# 2_6_0.net
KiCad netlist of a schematic drawn in Altium Designer
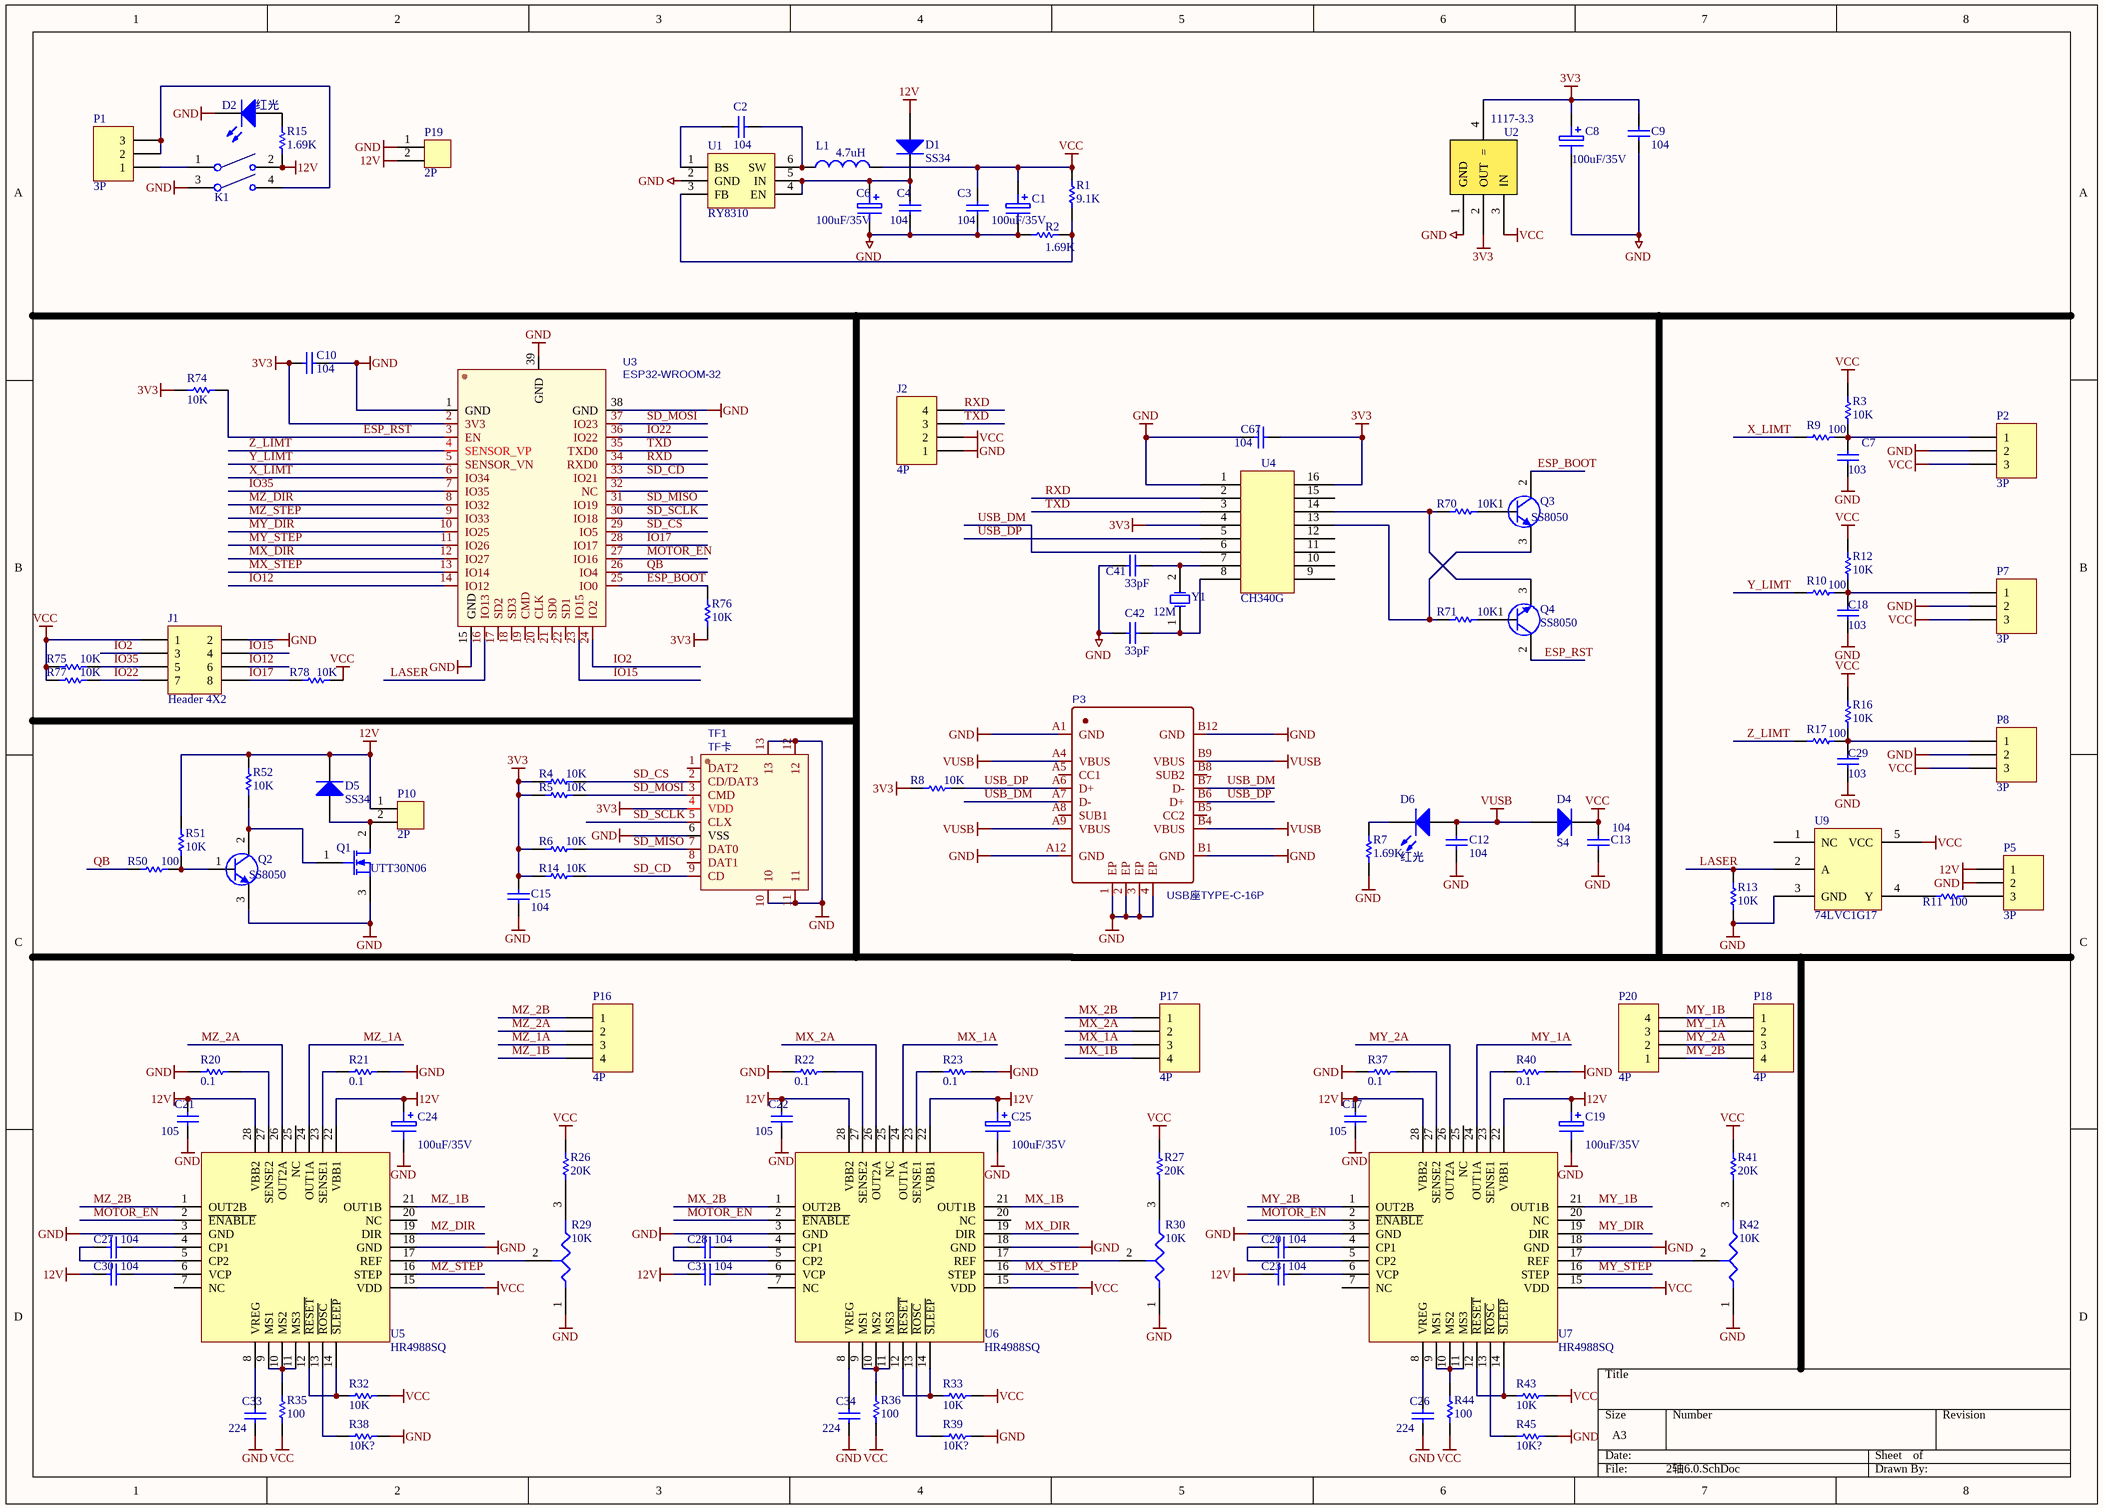
[diagram p0: 2轴6.0.SchDoc]

(export (version "E")
  (design (tool "Eeschema 10.0.6"))
  (components
    (comp (ref "C1") (value "100uF/35V") (footprint "电解电容贴片6x6") (libsource (lib "*") (part "ELECTRO1")))
    (comp (ref "C2") (value "104") (footprint "0603C") (libsource (lib "SCH封装库") (part "CAP")))
    (comp (ref "C3")
      (value "104")
      (footprint "0603C")
      (description "Capacitor (Semiconductor SIM Model)")
      (libsource (lib "Miscellaneous Devices") (part "Cap Semi"))
    )
    (comp (ref "C4") (value "104") (footprint "0603C") (libsource (lib "SCH封装库") (part "CAP")))
    (comp (ref "C6") (value "100uF/35V") (footprint "电解电容贴片6x6") (libsource (lib "*") (part "ELECTRO1")))
    (comp (ref "C7") (value "103") (footprint "0603C") (libsource (lib "SCH封装库") (part "CAP")))
    (comp (ref "C8") (value "100uF/35V") (footprint "电解电容贴片6x6") (libsource (lib "*") (part "ELECTRO1")))
    (comp (ref "C9")
      (value "104")
      (footprint "0603C")
      (description "Capacitor (Semiconductor SIM Model)")
      (libsource (lib "Miscellaneous Devices") (part "Cap Semi"))
    )
    (comp (ref "C10")
      (value "104")
      (footprint "0603C")
      (description "Capacitor (Semiconductor SIM Model)")
      (libsource (lib "Miscellaneous Devices") (part "Cap Semi"))
    )
    (comp (ref "C12")
      (value "104")
      (footprint "0603C")
      (description "Capacitor (Semiconductor SIM Model)")
      (libsource (lib "Miscellaneous Devices") (part "Cap Semi"))
    )
    (comp (ref "C13")
      (value "104")
      (footprint "0603C")
      (description "Capacitor (Semiconductor SIM Model)")
      (libsource (lib "Miscellaneous Devices") (part "Cap Semi"))
    )
    (comp (ref "C15")
      (value "104")
      (footprint "0603C")
      (description "Capacitor (Semiconductor SIM Model)")
      (libsource (lib "Miscellaneous Devices") (part "Cap Semi"))
    )
    (comp (ref "C17") (value "105") (footprint "0805C") (libsource (lib "SCH封装库") (part "CAP")))
    (comp (ref "C18") (value "103") (footprint "0603C") (libsource (lib "SCH封装库") (part "CAP")))
    (comp (ref "C19") (value "100uF/35V") (footprint "电解电容贴片6x6") (libsource (lib "*") (part "ELECTRO1")))
    (comp (ref "C20") (value "104") (footprint "0603C") (libsource (lib "SCH封装库") (part "CAP")))
    (comp (ref "C21") (value "105") (footprint "0805C") (libsource (lib "SCH封装库") (part "CAP")))
    (comp (ref "C22") (value "105") (footprint "0805C") (libsource (lib "SCH封装库") (part "CAP")))
    (comp (ref "C23") (value "104") (footprint "0603C") (libsource (lib "SCH封装库") (part "CAP")))
    (comp (ref "C24") (value "100uF/35V") (footprint "电解电容贴片6x6") (libsource (lib "*") (part "ELECTRO1")))
    (comp (ref "C25") (value "100uF/35V") (footprint "电解电容贴片6x6") (libsource (lib "*") (part "ELECTRO1")))
    (comp (ref "C26") (value "224") (footprint "0603C") (libsource (lib "SCH封装库") (part "CAP")))
    (comp (ref "C27") (value "104") (footprint "0603C") (libsource (lib "SCH封装库") (part "CAP")))
    (comp (ref "C28") (value "104") (footprint "0603C") (libsource (lib "SCH封装库") (part "CAP")))
    (comp (ref "C29") (value "103") (footprint "0603C") (libsource (lib "SCH封装库") (part "CAP")))
    (comp (ref "C30") (value "104") (footprint "0603C") (libsource (lib "SCH封装库") (part "CAP")))
    (comp (ref "C31") (value "104") (footprint "0603C") (libsource (lib "SCH封装库") (part "CAP")))
    (comp (ref "C33") (value "224") (footprint "0603C") (libsource (lib "SCH封装库") (part "CAP")))
    (comp (ref "C34") (value "224") (footprint "0603C") (libsource (lib "SCH封装库") (part "CAP")))
    (comp (ref "C41")
      (value "33pF")
      (footprint "0603C")
      (description "Capacitor (Semiconductor SIM Model)")
      (libsource (lib "Miscellaneous Devices") (part "Cap Semi"))
    )
    (comp (ref "C42")
      (value "33pF")
      (footprint "0603C")
      (description "Capacitor (Semiconductor SIM Model)")
      (libsource (lib "Miscellaneous Devices") (part "Cap Semi"))
    )
    (comp (ref "C67")
      (value "104")
      (footprint "0603C")
      (description "Capacitor (Semiconductor SIM Model)")
      (libsource (lib "Miscellaneous Devices") (part "Cap Semi"))
    )
    (comp (ref "D1") (value "SS34") (footprint "SMA") (libsource (lib "SCH封装库") (part "1N4148")))
    (comp (ref "D2") (value "红光") (footprint "0603LED") (libsource (lib "SCH封装库") (part "LED")))
    (comp (ref "D4") (value "S4") (footprint "SOD-123") (libsource (lib "SCH封装库") (part "1N4148")))
    (comp (ref "D5") (value "SS34") (footprint "SMA") (libsource (lib "SCH封装库") (part "1N4148")))
    (comp (ref "D6") (value "红光") (footprint "0603LED") (libsource (lib "SCH封装库") (part "LED")))
    (comp (ref "J1")
      (value "Header 4X2")
      (footprint "HDR2X4")
      (description "Header, 4-Pin, Dual row")
      (libsource (lib "Miscellaneous Connectors") (part "Header 4X2"))
    )
    (comp (ref "J2") (value "4P") (footprint "SIP4") (libsource (lib "") (part "4P_1")))
    (comp (ref "K1") (value "船形开关") (footprint "船形开关KCD1-104-4P") (libsource (lib "SCH封装库") (part "船形开关双刀")))
    (comp (ref "L1")
      (value "4.7uH")
      (footprint "电感贴片7x7")
      (description "Inductor")
      (libsource (lib "SCH封装库") (part "Inductor"))
    )
    (comp (ref "P1") (value "3P") (footprint "DC0044A") (libsource (lib "") (part "3P_1")))
    (comp (ref "P2") (value "3P") (footprint "HDR1X3_P") (libsource (lib "SCH封装库") (part "3P")))
    (comp (ref "P3")
      (value "USB座TYPE-C-16P")
      (footprint "USB-TYPE-C-16P")
      (fields
        (field (name "BOM_SUPPLIER PART") "C709358")
        (field (name "BOM_MANUFACTURER PART") "KH-TYPE-C-16P-T")
      )
      (libsource (lib "SCH封装库") (part "USB座TYPE-C-16P"))
    )
    (comp (ref "P5") (value "3P") (footprint "HDR1X3_P") (libsource (lib "SCH封装库") (part "3P")))
    (comp (ref "P7") (value "3P") (footprint "HDR1X3_P") (libsource (lib "SCH封装库") (part "3P")))
    (comp (ref "P8") (value "3P") (footprint "HDR1X3_P") (libsource (lib "SCH封装库") (part "3P")))
    (comp (ref "P10") (value "2P") (footprint "HDR1X2_P") (libsource (lib "SCH封装库") (part "2P")))
    (comp (ref "P16") (value "4P") (footprint "HDR1X4_P") (libsource (lib "SCH封装库") (part "4P")))
    (comp (ref "P17") (value "4P") (footprint "HDR1X4_P") (libsource (lib "SCH封装库") (part "4P")))
    (comp (ref "P18") (value "4P") (footprint "HDR1X4_P") (libsource (lib "SCH封装库") (part "4P")))
    (comp (ref "P19") (value "2P") (footprint "HDR1X2_P") (libsource (lib "SCH封装库") (part "2P")))
    (comp (ref "P20") (value "4P") (footprint "HDR1X4_P") (libsource (lib "") (part "4P_1")))
    (comp (ref "Q1")
      (value "UTT30N06")
      (footprint "TO-252")
      (description "N-Channel MOSFET")
      (libsource (lib "SCH封装库") (part "MOSFET-N"))
    )
    (comp (ref "Q2") (value "SS8050") (footprint "SOT-23") (libsource (lib "SCH封装库") (part "NPN")))
    (comp (ref "Q3") (value "SS8050") (footprint "SOT-23") (libsource (lib "SCH封装库") (part "NPN")))
    (comp (ref "Q4") (value "SS8050") (footprint "SOT-23") (libsource (lib "") (part "NPN_1")))
    (comp (ref "R1")
      (value "9.1K")
      (footprint "0603R")
      (description "Resistor")
      (libsource (lib "SCH封装库") (part "RES"))
    )
    (comp (ref "R2")
      (value "1.69K")
      (footprint "0603R")
      (description "Resistor")
      (libsource (lib "SCH封装库") (part "RES"))
    )
    (comp (ref "R3")
      (value "10K")
      (footprint "0603R")
      (description "Resistor")
      (libsource (lib "SCH封装库") (part "RES"))
    )
    (comp (ref "R4")
      (value "10K")
      (footprint "0603R")
      (description "Resistor")
      (libsource (lib "SCH封装库") (part "RES"))
    )
    (comp (ref "R5")
      (value "10K")
      (footprint "0603R")
      (description "Resistor")
      (libsource (lib "SCH封装库") (part "RES"))
    )
    (comp (ref "R6")
      (value "10K")
      (footprint "0603R")
      (description "Resistor")
      (libsource (lib "SCH封装库") (part "RES"))
    )
    (comp (ref "R7")
      (value "1.69K")
      (footprint "0603R")
      (description "Resistor")
      (libsource (lib "SCH封装库") (part "RES"))
    )
    (comp (ref "R8")
      (value "10K")
      (footprint "0603R")
      (description "Resistor")
      (libsource (lib "SCH封装库") (part "RES"))
    )
    (comp (ref "R9")
      (value "100")
      (footprint "0603R")
      (description "Resistor")
      (libsource (lib "SCH封装库") (part "RES"))
    )
    (comp (ref "R10")
      (value "100")
      (footprint "0603R")
      (description "Resistor")
      (libsource (lib "SCH封装库") (part "RES"))
    )
    (comp (ref "R11")
      (value "100")
      (footprint "0603R")
      (description "Resistor")
      (libsource (lib "SCH封装库") (part "RES"))
    )
    (comp (ref "R12")
      (value "10K")
      (footprint "0603R")
      (description "Resistor")
      (libsource (lib "SCH封装库") (part "RES"))
    )
    (comp (ref "R13")
      (value "10K")
      (footprint "0603R")
      (description "Resistor")
      (libsource (lib "SCH封装库") (part "RES"))
    )
    (comp (ref "R14")
      (value "10K")
      (footprint "0603R")
      (description "Resistor")
      (libsource (lib "SCH封装库") (part "RES"))
    )
    (comp (ref "R15")
      (value "1.69K")
      (footprint "0603R")
      (description "Resistor")
      (libsource (lib "SCH封装库") (part "RES"))
    )
    (comp (ref "R16")
      (value "10K")
      (footprint "0603R")
      (description "Resistor")
      (libsource (lib "SCH封装库") (part "RES"))
    )
    (comp (ref "R17")
      (value "100")
      (footprint "0603R")
      (description "Resistor")
      (libsource (lib "SCH封装库") (part "RES"))
    )
    (comp (ref "R20")
      (value "0.1")
      (footprint "0805R")
      (description "Resistor")
      (libsource (lib "SCH封装库") (part "RES"))
    )
    (comp (ref "R21")
      (value "0.1")
      (footprint "0805R")
      (description "Resistor")
      (libsource (lib "SCH封装库") (part "RES"))
    )
    (comp (ref "R22")
      (value "0.1")
      (footprint "0805R")
      (description "Resistor")
      (libsource (lib "SCH封装库") (part "RES"))
    )
    (comp (ref "R23")
      (value "0.1")
      (footprint "0805R")
      (description "Resistor")
      (libsource (lib "SCH封装库") (part "RES"))
    )
    (comp (ref "R26")
      (value "20K")
      (footprint "0603R")
      (description "Resistor")
      (libsource (lib "SCH封装库") (part "RES"))
    )
    (comp (ref "R27")
      (value "20K")
      (footprint "0603R")
      (description "Resistor")
      (libsource (lib "SCH封装库") (part "RES"))
    )
    (comp (ref "R29") (value "10K") (footprint "松下贴片电位器3x3") (libsource (lib "SCH封装库") (part "电位器")))
    (comp (ref "R30") (value "10K") (footprint "松下贴片电位器3x3") (libsource (lib "SCH封装库") (part "电位器")))
    (comp (ref "R32")
      (value "10K")
      (footprint "0603R")
      (description "Resistor")
      (libsource (lib "SCH封装库") (part "RES"))
    )
    (comp (ref "R33")
      (value "10K")
      (footprint "0603R")
      (description "Resistor")
      (libsource (lib "SCH封装库") (part "RES"))
    )
    (comp (ref "R35")
      (value "100")
      (footprint "0603R")
      (description "Resistor")
      (libsource (lib "SCH封装库") (part "RES"))
    )
    (comp (ref "R36")
      (value "100")
      (footprint "0603R")
      (description "Resistor")
      (libsource (lib "SCH封装库") (part "RES"))
    )
    (comp (ref "R37")
      (value "0.1")
      (footprint "0805R")
      (description "Resistor")
      (libsource (lib "SCH封装库") (part "RES"))
    )
    (comp (ref "R38")
      (value "10K?")
      (footprint "0603R")
      (description "Resistor")
      (libsource (lib "SCH封装库") (part "RES"))
    )
    (comp (ref "R39")
      (value "10K?")
      (footprint "0603R")
      (description "Resistor")
      (libsource (lib "SCH封装库") (part "RES"))
    )
    (comp (ref "R40")
      (value "0.1")
      (footprint "0805R")
      (description "Resistor")
      (libsource (lib "SCH封装库") (part "RES"))
    )
    (comp (ref "R41")
      (value "20K")
      (footprint "0603R")
      (description "Resistor")
      (libsource (lib "SCH封装库") (part "RES"))
    )
    (comp (ref "R42") (value "10K") (footprint "松下贴片电位器3x3") (libsource (lib "SCH封装库") (part "电位器")))
    (comp (ref "R43")
      (value "10K")
      (footprint "0603R")
      (description "Resistor")
      (libsource (lib "SCH封装库") (part "RES"))
    )
    (comp (ref "R44")
      (value "100")
      (footprint "0603R")
      (description "Resistor")
      (libsource (lib "SCH封装库") (part "RES"))
    )
    (comp (ref "R45")
      (value "10K?")
      (footprint "0603R")
      (description "Resistor")
      (libsource (lib "SCH封装库") (part "RES"))
    )
    (comp (ref "R50")
      (value "100")
      (footprint "0603R")
      (description "Resistor")
      (libsource (lib "SCH封装库") (part "RES"))
    )
    (comp (ref "R51")
      (value "10K")
      (footprint "0603R")
      (description "Resistor")
      (libsource (lib "SCH封装库") (part "RES"))
    )
    (comp (ref "R52")
      (value "10K")
      (footprint "0603R")
      (description "Resistor")
      (libsource (lib "SCH封装库") (part "RES"))
    )
    (comp (ref "R70")
      (value "10K")
      (footprint "0603R")
      (description "Resistor")
      (libsource (lib "SCH封装库") (part "RES"))
    )
    (comp (ref "R71")
      (value "10K")
      (footprint "0603R")
      (description "Resistor")
      (libsource (lib "SCH封装库") (part "RES"))
    )
    (comp (ref "R74")
      (value "10K")
      (footprint "0603R")
      (description "Resistor")
      (libsource (lib "SCH封装库") (part "RES"))
    )
    (comp (ref "R75")
      (value "10K")
      (footprint "0603R")
      (description "Resistor")
      (libsource (lib "SCH封装库") (part "RES"))
    )
    (comp (ref "R76")
      (value "10K")
      (footprint "0603R")
      (description "Resistor")
      (libsource (lib "SCH封装库") (part "RES"))
    )
    (comp (ref "R77")
      (value "10K")
      (footprint "0603R")
      (description "Resistor")
      (libsource (lib "SCH封装库") (part "RES"))
    )
    (comp (ref "R78")
      (value "10K")
      (footprint "0603R")
      (description "Resistor")
      (libsource (lib "SCH封装库") (part "RES"))
    )
    (comp (ref "TF1")
      (value "TF卡")
      (footprint "TF卡自弹式")
      (fields (field (name "BOM_SUPPLIER PART") "C410350") (field (name "BOM_MANUFACTURER PART") "TF-012"))
      (libsource (lib "SCH封装库") (part "TF-012"))
    )
    (comp (ref "U1") (value "RY8310") (footprint "SOT-23-6") (libsource (lib "SCH封装库") (part "RY8310")))
    (comp (ref "U2") (value "1117-3.3") (footprint "SOT-223") (libsource (lib "Party600") (part "LM1117")))
    (comp (ref "U3")
      (value "ESP32-WROOM-32")
      (footprint "WIFIM-SMD_38P-L25.5-W18.0-P1.27")
      (fields
        (field (name "BOM_SUPPLIER PART") "C473013")
        (field (name "BOM_MANUFACTURER PART") "ESP32-WROOM-32DC")
      )
      (libsource (lib "SCH封装库") (part "ESP32-WROOM-32DC"))
    )
    (comp (ref "U4") (value "CH340G") (footprint "SOP16") (libsource (lib "SCH封装库") (part "DIP16")))
    (comp (ref "U5") (value "HR4988SQ") (footprint "QFN28") (libsource (lib "SCH封装库") (part "HR4988")))
    (comp (ref "U6") (value "HR4988SQ") (footprint "QFN28") (libsource (lib "SCH封装库") (part "HR4988")))
    (comp (ref "U7") (value "HR4988SQ") (footprint "QFN28") (libsource (lib "SCH封装库") (part "HR4988")))
    (comp (ref "U9") (value "74LVC1G17") (footprint "SOT-23-5") (libsource (lib "SCH封装库") (part "74LVC1G17")))
    (comp (ref "Y1")
      (value "12M")
      (footprint "晶振贴片49SSMD")
      (description "Crystal Oscillator")
      (libsource (lib "Miscellaneous Devices") (part "XTAL"))
    )
  )
  (nets
    (net (code "1") (name "/ESP_BOOT") (class "Default")
      (node (ref "Q3") (pin "2") (pinfunction "C_2") (pintype "passive"))
      (node (ref "R76") (pin "2") (pinfunction "2_2") (pintype "passive"))
      (node (ref "U3") (pin "25") (pinfunction "IO0_25") (pintype "passive"))
    )
    (net (code "2") (name "/ESP_RST") (class "Default")
      (node (ref "Q4") (pin "2") (pinfunction "C_2") (pintype "passive"))
      (node (ref "R74") (pin "1") (pinfunction "1_1") (pintype "passive"))
      (node (ref "U3") (pin "3") (pinfunction "EN_3") (pintype "passive"))
    )
    (net (code "3") (name "/IO2") (class "Default")
      (node (ref "J1") (pin "3") (pinfunction "3_3") (pintype "passive"))
      (node (ref "U3") (pin "24") (pinfunction "IO2_24") (pintype "passive"))
    )
    (net (code "4") (name "/IO12") (class "Default")
      (node (ref "J1") (pin "6") (pinfunction "6_6") (pintype "passive"))
      (node (ref "U3") (pin "14") (pinfunction "IO12_14") (pintype "passive"))
    )
    (net (code "5") (name "/IO15") (class "Default")
      (node (ref "J1") (pin "4") (pinfunction "4_4") (pintype "passive"))
      (node (ref "U3") (pin "23") (pinfunction "IO15_23") (pintype "passive"))
    )
    (net (code "6") (name "/IO17") (class "Default")
      (node (ref "J1") (pin "8") (pinfunction "8_8") (pintype "passive"))
      (node (ref "R78") (pin "2") (pinfunction "2_2") (pintype "passive"))
      (node (ref "U3") (pin "28") (pinfunction "IO17_28") (pintype "passive"))
    )
    (net (code "7") (name "/IO22") (class "Default")
      (node (ref "J1") (pin "7") (pinfunction "7_7") (pintype "passive"))
      (node (ref "R77") (pin "1") (pinfunction "1_1") (pintype "passive"))
      (node (ref "U3") (pin "36") (pinfunction "IO22_36") (pintype "passive"))
    )
    (net (code "8") (name "/IO35") (class "Default")
      (node (ref "J1") (pin "5") (pinfunction "5_5") (pintype "passive"))
      (node (ref "R75") (pin "1") (pinfunction "1_1") (pintype "passive"))
      (node (ref "U3") (pin "7") (pinfunction "IO35_7") (pintype "passive"))
    )
    (net (code "9") (name "/LASER") (class "Default")
      (node (ref "R13") (pin "2") (pinfunction "2_2") (pintype "passive"))
      (node (ref "U3") (pin "16") (pinfunction "IO13_16") (pintype "passive"))
      (node (ref "U9") (pin "2") (pinfunction "A_2") (pintype "passive"))
    )
    (net (code "10") (name "/MOTOR_EN") (class "Default")
      (node (ref "U3") (pin "27") (pinfunction "IO16_27") (pintype "passive"))
      (node (ref "U5") (pin "2") (pinfunction "~{ENABLE}_2") (pintype "passive"))
      (node (ref "U6") (pin "2") (pinfunction "~{ENABLE}_2") (pintype "passive"))
      (node (ref "U7") (pin "2") (pinfunction "~{ENABLE}_2") (pintype "passive"))
    )
    (net (code "11") (name "/MX_1A") (class "Default")
      (node (ref "P17") (pin "3") (pinfunction "3_3") (pintype "passive"))
      (node (ref "U6") (pin "24") (pinfunction "OUT1A_24") (pintype "passive"))
    )
    (net (code "12") (name "/MX_1B") (class "Default")
      (node (ref "P17") (pin "4") (pinfunction "4_4") (pintype "passive"))
      (node (ref "U6") (pin "21") (pinfunction "OUT1B_21") (pintype "passive"))
    )
    (net (code "13") (name "/MX_2A") (class "Default")
      (node (ref "P17") (pin "2") (pinfunction "2_2") (pintype "passive"))
      (node (ref "U6") (pin "26") (pinfunction "OUT2A_26") (pintype "passive"))
    )
    (net (code "14") (name "/MX_2B") (class "Default")
      (node (ref "P17") (pin "1") (pinfunction "1_1") (pintype "passive"))
      (node (ref "U6") (pin "1") (pinfunction "OUT2B_1") (pintype "passive"))
    )
    (net (code "15") (name "/MX_DIR") (class "Default")
      (node (ref "U3") (pin "12") (pinfunction "IO27_12") (pintype "passive"))
      (node (ref "U6") (pin "19") (pinfunction "DIR_19") (pintype "passive"))
    )
    (net (code "16") (name "/MX_STEP") (class "Default")
      (node (ref "U3") (pin "13") (pinfunction "IO14_13") (pintype "passive"))
      (node (ref "U6") (pin "16") (pinfunction "STEP_16") (pintype "passive"))
    )
    (net (code "17") (name "/MY_1A") (class "Default")
      (node (ref "P18") (pin "2") (pinfunction "2_2") (pintype "passive"))
      (node (ref "P20") (pin "3") (pinfunction "3_3") (pintype "passive"))
      (node (ref "U7") (pin "24") (pinfunction "OUT1A_24") (pintype "passive"))
    )
    (net (code "18") (name "/MY_1B") (class "Default")
      (node (ref "P18") (pin "1") (pinfunction "1_1") (pintype "passive"))
      (node (ref "P20") (pin "4") (pinfunction "4_4") (pintype "passive"))
      (node (ref "U7") (pin "21") (pinfunction "OUT1B_21") (pintype "passive"))
    )
    (net (code "19") (name "/MY_2A") (class "Default")
      (node (ref "P18") (pin "3") (pinfunction "3_3") (pintype "passive"))
      (node (ref "P20") (pin "2") (pinfunction "2_2") (pintype "passive"))
      (node (ref "U7") (pin "26") (pinfunction "OUT2A_26") (pintype "passive"))
    )
    (net (code "20") (name "/MY_2B") (class "Default")
      (node (ref "P18") (pin "4") (pinfunction "4_4") (pintype "passive"))
      (node (ref "P20") (pin "1") (pinfunction "1_1") (pintype "passive"))
      (node (ref "U7") (pin "1") (pinfunction "OUT2B_1") (pintype "passive"))
    )
    (net (code "21") (name "/MY_DIR") (class "Default")
      (node (ref "U3") (pin "10") (pinfunction "IO25_10") (pintype "passive"))
      (node (ref "U7") (pin "19") (pinfunction "DIR_19") (pintype "passive"))
    )
    (net (code "22") (name "/MY_STEP") (class "Default")
      (node (ref "U3") (pin "11") (pinfunction "IO26_11") (pintype "passive"))
      (node (ref "U7") (pin "16") (pinfunction "STEP_16") (pintype "passive"))
    )
    (net (code "23") (name "/MZ_1A") (class "Default")
      (node (ref "P16") (pin "3") (pinfunction "3_3") (pintype "passive"))
      (node (ref "U5") (pin "24") (pinfunction "OUT1A_24") (pintype "passive"))
    )
    (net (code "24") (name "/MZ_1B") (class "Default")
      (node (ref "P16") (pin "4") (pinfunction "4_4") (pintype "passive"))
      (node (ref "U5") (pin "21") (pinfunction "OUT1B_21") (pintype "passive"))
    )
    (net (code "25") (name "/MZ_2A") (class "Default")
      (node (ref "P16") (pin "2") (pinfunction "2_2") (pintype "passive"))
      (node (ref "U5") (pin "26") (pinfunction "OUT2A_26") (pintype "passive"))
    )
    (net (code "26") (name "/MZ_2B") (class "Default")
      (node (ref "P16") (pin "1") (pinfunction "1_1") (pintype "passive"))
      (node (ref "U5") (pin "1") (pinfunction "OUT2B_1") (pintype "passive"))
    )
    (net (code "27") (name "/MZ_DIR") (class "Default")
      (node (ref "U3") (pin "8") (pinfunction "IO32_8") (pintype "passive"))
      (node (ref "U5") (pin "19") (pinfunction "DIR_19") (pintype "passive"))
    )
    (net (code "28") (name "/MZ_STEP") (class "Default")
      (node (ref "U3") (pin "9") (pinfunction "IO33_9") (pintype "passive"))
      (node (ref "U5") (pin "16") (pinfunction "STEP_16") (pintype "passive"))
    )
    (net (code "29") (name "/QB") (class "Default")
      (node (ref "R50") (pin "2") (pinfunction "2_2") (pintype "passive"))
      (node (ref "U3") (pin "26") (pinfunction "IO4_26") (pintype "passive"))
    )
    (net (code "30") (name "/RXD") (class "Default")
      (node (ref "J2") (pin "4") (pinfunction "4_4") (pintype "passive"))
      (node (ref "U3") (pin "34") (pinfunction "RXD0_34") (pintype "passive"))
      (node (ref "U4") (pin "2") (pinfunction "2_2") (pintype "passive"))
    )
    (net (code "31") (name "/SD_CD") (class "Default")
      (node (ref "R14") (pin "1") (pinfunction "1_1") (pintype "passive"))
      (node (ref "TF1") (pin "9") (pinfunction "CD_9") (pintype "passive"))
      (node (ref "U3") (pin "33") (pinfunction "IO21_33") (pintype "passive"))
    )
    (net (code "32") (name "/SD_CS") (class "Default")
      (node (ref "R4") (pin "1") (pinfunction "1_1") (pintype "passive"))
      (node (ref "TF1") (pin "2") (pinfunction "CD/DAT3_2") (pintype "passive"))
      (node (ref "U3") (pin "29") (pinfunction "IO5_29") (pintype "passive"))
    )
    (net (code "33") (name "/SD_MISO") (class "Default")
      (node (ref "R6") (pin "1") (pinfunction "1_1") (pintype "passive"))
      (node (ref "TF1") (pin "7") (pinfunction "DAT0_7") (pintype "passive"))
      (node (ref "U3") (pin "31") (pinfunction "IO19_31") (pintype "passive"))
    )
    (net (code "34") (name "/SD_MOSI") (class "Default")
      (node (ref "R5") (pin "1") (pinfunction "1_1") (pintype "passive"))
      (node (ref "TF1") (pin "3") (pinfunction "CMD_3") (pintype "passive"))
      (node (ref "U3") (pin "37") (pinfunction "IO23_37") (pintype "passive"))
    )
    (net (code "35") (name "/SD_SCLK") (class "Default")
      (node (ref "TF1") (pin "5") (pinfunction "CLX_5") (pintype "passive"))
      (node (ref "U3") (pin "30") (pinfunction "IO18_30") (pintype "passive"))
    )
    (net (code "36") (name "/TXD") (class "Default")
      (node (ref "J2") (pin "3") (pinfunction "3_3") (pintype "passive"))
      (node (ref "U3") (pin "35") (pinfunction "TXD0_35") (pintype "passive"))
      (node (ref "U4") (pin "3") (pinfunction "3_3") (pintype "passive"))
    )
    (net (code "37") (name "/USB_DM") (class "Default")
      (node (ref "P3") (pin "A7") (pinfunction "D-_A7") (pintype "passive"))
      (node (ref "P3") (pin "B7") (pinfunction "D-_B7") (pintype "passive"))
      (node (ref "U4") (pin "6") (pinfunction "6_6") (pintype "passive"))
    )
    (net (code "38") (name "/USB_DP") (class "Default")
      (node (ref "P3") (pin "A6") (pinfunction "D+_A6") (pintype "passive"))
      (node (ref "P3") (pin "B6") (pinfunction "D+_B6") (pintype "passive"))
      (node (ref "R8") (pin "2") (pinfunction "2_2") (pintype "passive"))
      (node (ref "U4") (pin "5") (pinfunction "5_5") (pintype "passive"))
    )
    (net (code "39") (name "/X_LIMT") (class "Default")
      (node (ref "R9") (pin "2") (pinfunction "2_2") (pintype "passive"))
      (node (ref "U3") (pin "6") (pinfunction "IO34_6") (pintype "passive"))
    )
    (net (code "40") (name "/Y_LIMT") (class "Default")
      (node (ref "R10") (pin "2") (pinfunction "2_2") (pintype "passive"))
      (node (ref "U3") (pin "5") (pinfunction "SENSOR_VN_5") (pintype "passive"))
    )
    (net (code "41") (name "/Z_LIMT") (class "Default")
      (node (ref "R17") (pin "2") (pinfunction "2_2") (pintype "passive"))
      (node (ref "U3") (pin "4") (pinfunction "SENSOR_VP_4") (pintype "passive"))
    )
    (net (code "42") (name "3V3") (class "Default")
      (node (ref "C10") (pin "2") (pinfunction "2_2") (pintype "passive"))
      (node (ref "C15") (pin "2") (pinfunction "2_2") (pintype "passive"))
      (node (ref "C67") (pin "2") (pinfunction "2_2") (pintype "passive"))
      (node (ref "C8") (pin "1") (pintype "passive"))
      (node (ref "C9") (pin "2") (pinfunction "2_2") (pintype "passive"))
      (node (ref "R14") (pin "2") (pinfunction "2_2") (pintype "passive"))
      (node (ref "R4") (pin "2") (pinfunction "2_2") (pintype "passive"))
      (node (ref "R5") (pin "2") (pinfunction "2_2") (pintype "passive"))
      (node (ref "R6") (pin "2") (pinfunction "2_2") (pintype "passive"))
      (node (ref "R74") (pin "2") (pinfunction "2_2") (pintype "passive"))
      (node (ref "R76") (pin "1") (pinfunction "1_1") (pintype "passive"))
      (node (ref "R8") (pin "1") (pinfunction "1_1") (pintype "passive"))
      (node (ref "TF1") (pin "4") (pinfunction "VDD_4") (pintype "passive"))
      (node (ref "U2") (pin "2") (pinfunction "OUT_2") (pintype "power_in"))
      (node (ref "U2") (pin "4") (pinfunction "=_4") (pintype "power_in"))
      (node (ref "U3") (pin "2") (pinfunction "3V3_2") (pintype "passive"))
      (node (ref "U4") (pin "16") (pinfunction "16_16") (pintype "passive"))
      (node (ref "U4") (pin "4") (pinfunction "4_4") (pintype "passive"))
    )
    (net (code "43") (name "12V") (class "Default")
      (node (ref "C17") (pin "1") (pinfunction "1_1") (pintype "passive"))
      (node (ref "C19") (pin "1") (pintype "passive"))
      (node (ref "C21") (pin "1") (pinfunction "1_1") (pintype "passive"))
      (node (ref "C22") (pin "1") (pinfunction "1_1") (pintype "passive"))
      (node (ref "C23") (pin "2") (pinfunction "2_2") (pintype "passive"))
      (node (ref "C24") (pin "1") (pintype "passive"))
      (node (ref "C25") (pin "1") (pintype "passive"))
      (node (ref "C30") (pin "2") (pinfunction "2_2") (pintype "passive"))
      (node (ref "C31") (pin "2") (pinfunction "2_2") (pintype "passive"))
      (node (ref "D1") (pin "1") (pinfunction "1_1") (pintype "passive"))
      (node (ref "D5") (pin "2") (pinfunction "2_2") (pintype "passive"))
      (node (ref "K1") (pin "2") (pinfunction "2_2") (pintype "passive"))
      (node (ref "P10") (pin "1") (pintype "passive"))
      (node (ref "P19") (pin "2") (pintype "passive"))
      (node (ref "P5") (pin "1") (pinfunction "1_1") (pintype "passive"))
      (node (ref "R15") (pin "2") (pinfunction "2_2") (pintype "passive"))
      (node (ref "R51") (pin "1") (pinfunction "1_1") (pintype "passive"))
      (node (ref "R52") (pin "1") (pinfunction "1_1") (pintype "passive"))
      (node (ref "U5") (pin "22") (pinfunction "VBB1_22") (pintype "passive"))
      (node (ref "U5") (pin "28") (pinfunction "VBB2_28") (pintype "passive"))
      (node (ref "U6") (pin "22") (pinfunction "VBB1_22") (pintype "passive"))
      (node (ref "U6") (pin "28") (pinfunction "VBB2_28") (pintype "passive"))
      (node (ref "U7") (pin "22") (pinfunction "VBB1_22") (pintype "passive"))
      (node (ref "U7") (pin "28") (pinfunction "VBB2_28") (pintype "passive"))
    )
    (net (code "44") (name "GND") (class "Default")
      (node (ref "C1") (pin "2") (pintype "passive"))
      (node (ref "C10") (pin "1") (pinfunction "1_1") (pintype "passive"))
      (node (ref "C12") (pin "1") (pinfunction "1_1") (pintype "passive"))
      (node (ref "C13") (pin "1") (pinfunction "1_1") (pintype "passive"))
      (node (ref "C15") (pin "1") (pinfunction "1_1") (pintype "passive"))
      (node (ref "C17") (pin "2") (pinfunction "2_2") (pintype "passive"))
      (node (ref "C18") (pin "1") (pinfunction "1_1") (pintype "passive"))
      (node (ref "C19") (pin "2") (pintype "passive"))
      (node (ref "C21") (pin "2") (pinfunction "2_2") (pintype "passive"))
      (node (ref "C22") (pin "2") (pinfunction "2_2") (pintype "passive"))
      (node (ref "C24") (pin "2") (pintype "passive"))
      (node (ref "C25") (pin "2") (pintype "passive"))
      (node (ref "C26") (pin "2") (pinfunction "2_2") (pintype "passive"))
      (node (ref "C29") (pin "1") (pinfunction "1_1") (pintype "passive"))
      (node (ref "C3") (pin "1") (pinfunction "1_1") (pintype "passive"))
      (node (ref "C33") (pin "2") (pinfunction "2_2") (pintype "passive"))
      (node (ref "C34") (pin "2") (pinfunction "2_2") (pintype "passive"))
      (node (ref "C4") (pin "2") (pinfunction "2_2") (pintype "passive"))
      (node (ref "C41") (pin "2") (pinfunction "2_2") (pintype "passive"))
      (node (ref "C42") (pin "2") (pinfunction "2_2") (pintype "passive"))
      (node (ref "C6") (pin "2") (pintype "passive"))
      (node (ref "C67") (pin "1") (pinfunction "1_1") (pintype "passive"))
      (node (ref "C7") (pin "1") (pinfunction "1_1") (pintype "passive"))
      (node (ref "C8") (pin "2") (pintype "passive"))
      (node (ref "C9") (pin "1") (pinfunction "1_1") (pintype "passive"))
      (node (ref "D2") (pin "2") (pinfunction "2_2") (pintype "passive"))
      (node (ref "J1") (pin "2") (pinfunction "2_2") (pintype "passive"))
      (node (ref "J2") (pin "1") (pinfunction "1_1") (pintype "passive"))
      (node (ref "K1") (pin "3") (pinfunction "3_3") (pintype "passive"))
      (node (ref "P19") (pin "1") (pintype "passive"))
      (node (ref "P2") (pin "2") (pinfunction "2_2") (pintype "passive"))
      (node (ref "P3") (pin "1") (pinfunction "EP_1") (pintype "passive"))
      (node (ref "P3") (pin "2") (pinfunction "EP_2") (pintype "passive"))
      (node (ref "P3") (pin "3") (pinfunction "EP_3") (pintype "passive"))
      (node (ref "P3") (pin "4") (pinfunction "EP_4") (pintype "passive"))
      (node (ref "P3") (pin "A1") (pinfunction "GND_A1") (pintype "passive"))
      (node (ref "P3") (pin "A12") (pinfunction "GND_A12") (pintype "passive"))
      (node (ref "P3") (pin "B1") (pinfunction "GND_B1") (pintype "passive"))
      (node (ref "P3") (pin "B12") (pinfunction "GND_B12") (pintype "passive"))
      (node (ref "P5") (pin "2") (pinfunction "2_2") (pintype "passive"))
      (node (ref "P7") (pin "2") (pinfunction "2_2") (pintype "passive"))
      (node (ref "P8") (pin "2") (pinfunction "2_2") (pintype "passive"))
      (node (ref "Q1") (pin "3") (pinfunction "S_3") (pintype "passive"))
      (node (ref "Q2") (pin "3") (pinfunction "E_3") (pintype "passive"))
      (node (ref "R13") (pin "1") (pinfunction "1_1") (pintype "passive"))
      (node (ref "R2") (pin "1") (pinfunction "1_1") (pintype "passive"))
      (node (ref "R20") (pin "2") (pinfunction "2_2") (pintype "passive"))
      (node (ref "R21") (pin "1") (pinfunction "1_1") (pintype "passive"))
      (node (ref "R22") (pin "2") (pinfunction "2_2") (pintype "passive"))
      (node (ref "R23") (pin "1") (pinfunction "1_1") (pintype "passive"))
      (node (ref "R29") (pin "1") (pinfunction "A_1") (pintype "passive"))
      (node (ref "R30") (pin "1") (pinfunction "A_1") (pintype "passive"))
      (node (ref "R37") (pin "2") (pinfunction "2_2") (pintype "passive"))
      (node (ref "R38") (pin "2") (pinfunction "2_2") (pintype "passive"))
      (node (ref "R39") (pin "2") (pinfunction "2_2") (pintype "passive"))
      (node (ref "R40") (pin "1") (pinfunction "1_1") (pintype "passive"))
      (node (ref "R42") (pin "1") (pinfunction "A_1") (pintype "passive"))
      (node (ref "R45") (pin "2") (pinfunction "2_2") (pintype "passive"))
      (node (ref "R7") (pin "1") (pinfunction "1_1") (pintype "passive"))
      (node (ref "TF1") (pin "10") (pinfunction "10_10") (pintype "passive"))
      (node (ref "TF1") (pin "11") (pinfunction "11_11") (pintype "passive"))
      (node (ref "TF1") (pin "12") (pinfunction "12_12") (pintype "passive"))
      (node (ref "TF1") (pin "13") (pinfunction "13_13") (pintype "passive"))
      (node (ref "TF1") (pin "6") (pinfunction "VSS_6") (pintype "passive"))
      (node (ref "U1") (pin "2") (pinfunction "GND_2") (pintype "passive"))
      (node (ref "U2") (pin "1") (pinfunction "GND_1") (pintype "power_in"))
      (node (ref "U3") (pin "1") (pinfunction "GND_1") (pintype "passive"))
      (node (ref "U3") (pin "15") (pinfunction "GND_15") (pintype "passive"))
      (node (ref "U3") (pin "38") (pinfunction "GND_38") (pintype "passive"))
      (node (ref "U3") (pin "39") (pinfunction "GND_39") (pintype "passive"))
      (node (ref "U4") (pin "1") (pinfunction "1_1") (pintype "passive"))
      (node (ref "U5") (pin "18") (pinfunction "GND_18") (pintype "passive"))
      (node (ref "U5") (pin "3") (pinfunction "GND_3") (pintype "passive"))
      (node (ref "U6") (pin "18") (pinfunction "GND_18") (pintype "passive"))
      (node (ref "U6") (pin "3") (pinfunction "GND_3") (pintype "passive"))
      (node (ref "U7") (pin "18") (pinfunction "GND_18") (pintype "passive"))
      (node (ref "U7") (pin "3") (pinfunction "GND_3") (pintype "passive"))
      (node (ref "U9") (pin "3") (pinfunction "GND_3") (pintype "passive"))
    )
    (net (code "45") (name "Net-(C7-Pad2)") (class "Default")
      (node (ref "C7") (pin "2") (pinfunction "2_2") (pintype "passive"))
      (node (ref "P2") (pin "1") (pinfunction "1_1") (pintype "passive"))
      (node (ref "R3") (pin "1") (pinfunction "1_1") (pintype "passive"))
      (node (ref "R9") (pin "1") (pinfunction "1_1") (pintype "passive"))
    )
    (net (code "46") (name "Net-(C18-Pad2)") (class "Default")
      (node (ref "C18") (pin "2") (pinfunction "2_2") (pintype "passive"))
      (node (ref "P7") (pin "1") (pinfunction "1_1") (pintype "passive"))
      (node (ref "R10") (pin "1") (pinfunction "1_1") (pintype "passive"))
      (node (ref "R12") (pin "1") (pinfunction "1_1") (pintype "passive"))
    )
    (net (code "47") (name "Net-(C29-Pad2)") (class "Default")
      (node (ref "C29") (pin "2") (pinfunction "2_2") (pintype "passive"))
      (node (ref "P8") (pin "1") (pinfunction "1_1") (pintype "passive"))
      (node (ref "R16") (pin "1") (pinfunction "1_1") (pintype "passive"))
      (node (ref "R17") (pin "1") (pinfunction "1_1") (pintype "passive"))
    )
    (net (code "48") (name "Net-(D2-Pad1)") (class "Default")
      (node (ref "D2") (pin "1") (pinfunction "1_1") (pintype "passive"))
      (node (ref "R15") (pin "1") (pinfunction "1_1") (pintype "passive"))
    )
    (net (code "49") (name "Net-(D6-Pad2)") (class "Default")
      (node (ref "D6") (pin "2") (pinfunction "2_2") (pintype "passive"))
      (node (ref "R7") (pin "2") (pinfunction "2_2") (pintype "passive"))
    )
    (net (code "50") (name "Net-(K1-Pad1)") (class "Default")
      (node (ref "K1") (pin "1") (pinfunction "1_1") (pintype "passive"))
      (node (ref "P1") (pin "1") (pinfunction "1_1") (pintype "passive"))
    )
    (net (code "51") (name "Net-(K1-Pad4)") (class "Default")
      (node (ref "K1") (pin "4") (pinfunction "4_4") (pintype "passive"))
      (node (ref "P1") (pin "2") (pinfunction "2_2") (pintype "passive"))
      (node (ref "P1") (pin "3") (pinfunction "3_3") (pintype "passive"))
    )
    (net (code "52") (name "Net-(P5-Pad3)") (class "Default")
      (node (ref "P5") (pin "3") (pinfunction "3_3") (pintype "passive"))
      (node (ref "R11") (pin "2") (pinfunction "2_2") (pintype "passive"))
    )
    (net (code "53") (name "Net-(Q1-D)") (class "Default")
      (node (ref "D5") (pin "1") (pinfunction "1_1") (pintype "passive"))
      (node (ref "P10") (pin "2") (pintype "passive"))
      (node (ref "Q1") (pin "2") (pinfunction "D_2") (pintype "passive"))
    )
    (net (code "54") (name "Net-(Q1-G)") (class "Default")
      (node (ref "Q1") (pin "1") (pinfunction "G_1") (pintype "passive"))
      (node (ref "Q2") (pin "2") (pinfunction "C_2") (pintype "passive"))
      (node (ref "R52") (pin "2") (pinfunction "2_2") (pintype "passive"))
    )
    (net (code "55") (name "Net-(Q2-B)") (class "Default")
      (node (ref "Q2") (pin "1") (pinfunction "B_1") (pintype "passive"))
      (node (ref "R50") (pin "1") (pinfunction "1_1") (pintype "passive"))
      (node (ref "R51") (pin "2") (pinfunction "2_2") (pintype "passive"))
    )
    (net (code "56") (name "Net-(Q3-B)") (class "Default")
      (node (ref "Q3") (pin "1") (pinfunction "B_1") (pintype "passive"))
      (node (ref "R70") (pin "1") (pinfunction "1_1") (pintype "passive"))
    )
    (net (code "57") (name "Net-(Q3-E)") (class "Default")
      (node (ref "Q3") (pin "3") (pinfunction "E_3") (pintype "passive"))
      (node (ref "R71") (pin "2") (pinfunction "2_2") (pintype "passive"))
      (node (ref "U4") (pin "13") (pinfunction "13_13") (pintype "passive"))
    )
    (net (code "58") (name "Net-(Q4-B)") (class "Default")
      (node (ref "Q4") (pin "1") (pinfunction "B_1") (pintype "passive"))
      (node (ref "R71") (pin "1") (pinfunction "1_1") (pintype "passive"))
    )
    (net (code "59") (name "Net-(Q4-E)") (class "Default")
      (node (ref "Q4") (pin "3") (pinfunction "E_3") (pintype "passive"))
      (node (ref "R70") (pin "2") (pinfunction "2_2") (pintype "passive"))
      (node (ref "U4") (pin "14") (pinfunction "14_14") (pintype "passive"))
    )
    (net (code "60") (name "Net-(R29-B)") (class "Default")
      (node (ref "R26") (pin "1") (pinfunction "1_1") (pintype "passive"))
      (node (ref "R29") (pin "3") (pinfunction "B_3") (pintype "passive"))
    )
    (net (code "61") (name "Net-(R29-TAP)") (class "Default")
      (node (ref "R29") (pin "2") (pinfunction "TAP_2") (pintype "passive"))
      (node (ref "U5") (pin "17") (pinfunction "REF_17") (pintype "passive"))
    )
    (net (code "62") (name "Net-(R30-B)") (class "Default")
      (node (ref "R27") (pin "1") (pinfunction "1_1") (pintype "passive"))
      (node (ref "R30") (pin "3") (pinfunction "B_3") (pintype "passive"))
    )
    (net (code "63") (name "Net-(R30-TAP)") (class "Default")
      (node (ref "R30") (pin "2") (pinfunction "TAP_2") (pintype "passive"))
      (node (ref "U6") (pin "17") (pinfunction "REF_17") (pintype "passive"))
    )
    (net (code "64") (name "Net-(R42-B)") (class "Default")
      (node (ref "R41") (pin "1") (pinfunction "1_1") (pintype "passive"))
      (node (ref "R42") (pin "3") (pinfunction "B_3") (pintype "passive"))
    )
    (net (code "65") (name "Net-(R42-TAP)") (class "Default")
      (node (ref "R42") (pin "2") (pinfunction "TAP_2") (pintype "passive"))
      (node (ref "U7") (pin "17") (pinfunction "REF_17") (pintype "passive"))
    )
    (net (code "66") (name "Net-(U1-BS)") (class "Default")
      (node (ref "C2") (pin "2") (pinfunction "2_2") (pintype "passive"))
      (node (ref "U1") (pin "1") (pinfunction "BS_1") (pintype "passive"))
    )
    (net (code "67") (name "Net-(U1-EN)") (class "Default")
      (node (ref "C4") (pin "1") (pinfunction "1_1") (pintype "passive"))
      (node (ref "C6") (pin "1") (pintype "passive"))
      (node (ref "D1") (pin "2") (pinfunction "2_2") (pintype "passive"))
      (node (ref "U1") (pin "4") (pinfunction "EN_4") (pintype "passive"))
      (node (ref "U1") (pin "5") (pinfunction "IN_5") (pintype "passive"))
    )
    (net (code "68") (name "Net-(U1-FB)") (class "Default")
      (node (ref "R1") (pin "1") (pinfunction "1_1") (pintype "passive"))
      (node (ref "R2") (pin "2") (pinfunction "2_2") (pintype "passive"))
      (node (ref "U1") (pin "3") (pinfunction "FB_3") (pintype "passive"))
    )
    (net (code "69") (name "Net-(U1-SW)") (class "Default")
      (node (ref "C2") (pin "1") (pinfunction "1_1") (pintype "passive"))
      (node (ref "L1") (pin "1") (pinfunction "1_1") (pintype "passive"))
      (node (ref "U1") (pin "6") (pinfunction "SW_6") (pintype "passive"))
    )
    (net (code "70") (name "Net-(U5-CP1)") (class "Default")
      (node (ref "C27") (pin "1") (pinfunction "1_1") (pintype "passive"))
      (node (ref "U5") (pin "4") (pinfunction "CP1_4") (pintype "passive"))
    )
    (net (code "71") (name "Net-(U5-CP2)") (class "Default")
      (node (ref "C27") (pin "2") (pinfunction "2_2") (pintype "passive"))
      (node (ref "U5") (pin "5") (pinfunction "CP2_5") (pintype "passive"))
    )
    (net (code "72") (name "Net-(U5-MS1)") (class "Default")
      (node (ref "R35") (pin "2") (pinfunction "2_2") (pintype "passive"))
      (node (ref "U5") (pin "10") (pinfunction "MS2_10") (pintype "passive"))
      (node (ref "U5") (pin "11") (pinfunction "MS3_11") (pintype "passive"))
      (node (ref "U5") (pin "9") (pinfunction "MS1_9") (pintype "passive"))
    )
    (net (code "73") (name "Net-(U5-SENSE1)") (class "Default")
      (node (ref "R21") (pin "2") (pinfunction "2_2") (pintype "passive"))
      (node (ref "U5") (pin "23") (pinfunction "SENSE1_23") (pintype "passive"))
    )
    (net (code "74") (name "Net-(U5-SENSE2)") (class "Default")
      (node (ref "R20") (pin "1") (pinfunction "1_1") (pintype "passive"))
      (node (ref "U5") (pin "27") (pinfunction "SENSE2_27") (pintype "passive"))
    )
    (net (code "75") (name "Net-(U5-VCP)") (class "Default")
      (node (ref "C30") (pin "1") (pinfunction "1_1") (pintype "passive"))
      (node (ref "U5") (pin "6") (pinfunction "VCP_6") (pintype "passive"))
    )
    (net (code "76") (name "Net-(U5-VREG)") (class "Default")
      (node (ref "C33") (pin "1") (pinfunction "1_1") (pintype "passive"))
      (node (ref "U5") (pin "8") (pinfunction "VREG_8") (pintype "passive"))
    )
    (net (code "77") (name "Net-(U5-~{RESET})") (class "Default")
      (node (ref "R32") (pin "2") (pinfunction "2_2") (pintype "passive"))
      (node (ref "U5") (pin "12") (pinfunction "~{RESET}_12") (pintype "passive"))
      (node (ref "U5") (pin "14") (pinfunction "~{SLEEP}_14") (pintype "passive"))
    )
    (net (code "78") (name "Net-(U5-~{ROSC})") (class "Default")
      (node (ref "R38") (pin "1") (pinfunction "1_1") (pintype "passive"))
      (node (ref "U5") (pin "13") (pinfunction "~{ROSC}_13") (pintype "passive"))
    )
    (net (code "79") (name "Net-(U6-CP1)") (class "Default")
      (node (ref "C28") (pin "1") (pinfunction "1_1") (pintype "passive"))
      (node (ref "U6") (pin "4") (pinfunction "CP1_4") (pintype "passive"))
    )
    (net (code "80") (name "Net-(U6-CP2)") (class "Default")
      (node (ref "C28") (pin "2") (pinfunction "2_2") (pintype "passive"))
      (node (ref "U6") (pin "5") (pinfunction "CP2_5") (pintype "passive"))
    )
    (net (code "81") (name "Net-(U6-MS1)") (class "Default")
      (node (ref "R36") (pin "2") (pinfunction "2_2") (pintype "passive"))
      (node (ref "U6") (pin "10") (pinfunction "MS2_10") (pintype "passive"))
      (node (ref "U6") (pin "11") (pinfunction "MS3_11") (pintype "passive"))
      (node (ref "U6") (pin "9") (pinfunction "MS1_9") (pintype "passive"))
    )
    (net (code "82") (name "Net-(U6-SENSE1)") (class "Default")
      (node (ref "R23") (pin "2") (pinfunction "2_2") (pintype "passive"))
      (node (ref "U6") (pin "23") (pinfunction "SENSE1_23") (pintype "passive"))
    )
    (net (code "83") (name "Net-(U6-SENSE2)") (class "Default")
      (node (ref "R22") (pin "1") (pinfunction "1_1") (pintype "passive"))
      (node (ref "U6") (pin "27") (pinfunction "SENSE2_27") (pintype "passive"))
    )
    (net (code "84") (name "Net-(U6-VCP)") (class "Default")
      (node (ref "C31") (pin "1") (pinfunction "1_1") (pintype "passive"))
      (node (ref "U6") (pin "6") (pinfunction "VCP_6") (pintype "passive"))
    )
    (net (code "85") (name "Net-(U6-VREG)") (class "Default")
      (node (ref "C34") (pin "1") (pinfunction "1_1") (pintype "passive"))
      (node (ref "U6") (pin "8") (pinfunction "VREG_8") (pintype "passive"))
    )
    (net (code "86") (name "Net-(U6-~{RESET})") (class "Default")
      (node (ref "R33") (pin "2") (pinfunction "2_2") (pintype "passive"))
      (node (ref "U6") (pin "12") (pinfunction "~{RESET}_12") (pintype "passive"))
      (node (ref "U6") (pin "14") (pinfunction "~{SLEEP}_14") (pintype "passive"))
    )
    (net (code "87") (name "Net-(U6-~{ROSC})") (class "Default")
      (node (ref "R39") (pin "1") (pinfunction "1_1") (pintype "passive"))
      (node (ref "U6") (pin "13") (pinfunction "~{ROSC}_13") (pintype "passive"))
    )
    (net (code "88") (name "Net-(U7-CP1)") (class "Default")
      (node (ref "C20") (pin "1") (pinfunction "1_1") (pintype "passive"))
      (node (ref "U7") (pin "4") (pinfunction "CP1_4") (pintype "passive"))
    )
    (net (code "89") (name "Net-(U7-CP2)") (class "Default")
      (node (ref "C20") (pin "2") (pinfunction "2_2") (pintype "passive"))
      (node (ref "U7") (pin "5") (pinfunction "CP2_5") (pintype "passive"))
    )
    (net (code "90") (name "Net-(U7-MS1)") (class "Default")
      (node (ref "R44") (pin "2") (pinfunction "2_2") (pintype "passive"))
      (node (ref "U7") (pin "10") (pinfunction "MS2_10") (pintype "passive"))
      (node (ref "U7") (pin "11") (pinfunction "MS3_11") (pintype "passive"))
      (node (ref "U7") (pin "9") (pinfunction "MS1_9") (pintype "passive"))
    )
    (net (code "91") (name "Net-(U7-SENSE1)") (class "Default")
      (node (ref "R40") (pin "2") (pinfunction "2_2") (pintype "passive"))
      (node (ref "U7") (pin "23") (pinfunction "SENSE1_23") (pintype "passive"))
    )
    (net (code "92") (name "Net-(U7-SENSE2)") (class "Default")
      (node (ref "R37") (pin "1") (pinfunction "1_1") (pintype "passive"))
      (node (ref "U7") (pin "27") (pinfunction "SENSE2_27") (pintype "passive"))
    )
    (net (code "93") (name "Net-(U7-VCP)") (class "Default")
      (node (ref "C23") (pin "1") (pinfunction "1_1") (pintype "passive"))
      (node (ref "U7") (pin "6") (pinfunction "VCP_6") (pintype "passive"))
    )
    (net (code "94") (name "Net-(U7-VREG)") (class "Default")
      (node (ref "C26") (pin "1") (pinfunction "1_1") (pintype "passive"))
      (node (ref "U7") (pin "8") (pinfunction "VREG_8") (pintype "passive"))
    )
    (net (code "95") (name "Net-(U7-~{RESET})") (class "Default")
      (node (ref "R43") (pin "2") (pinfunction "2_2") (pintype "passive"))
      (node (ref "U7") (pin "12") (pinfunction "~{RESET}_12") (pintype "passive"))
      (node (ref "U7") (pin "14") (pinfunction "~{SLEEP}_14") (pintype "passive"))
    )
    (net (code "96") (name "Net-(U7-~{ROSC})") (class "Default")
      (node (ref "R45") (pin "1") (pinfunction "1_1") (pintype "passive"))
      (node (ref "U7") (pin "13") (pinfunction "~{ROSC}_13") (pintype "passive"))
    )
    (net (code "97") (name "Net-(U9-Y)") (class "Default")
      (node (ref "R11") (pin "1") (pinfunction "1_1") (pintype "passive"))
      (node (ref "U9") (pin "4") (pinfunction "Y_4") (pintype "passive"))
    )
    (net (code "98") (name "Net-(Y1-OSC1)") (class "Default")
      (node (ref "C42") (pin "1") (pinfunction "1_1") (pintype "passive"))
      (node (ref "U4") (pin "8") (pinfunction "8_8") (pintype "passive"))
      (node (ref "Y1") (pin "1") (pinfunction "OSC1_1") (pintype "passive"))
    )
    (net (code "99") (name "Net-(Y1-OSC2)") (class "Default")
      (node (ref "C41") (pin "1") (pinfunction "1_1") (pintype "passive"))
      (node (ref "U4") (pin "7") (pinfunction "7_7") (pintype "passive"))
      (node (ref "Y1") (pin "2") (pinfunction "OSC2_2") (pintype "passive"))
    )
    (net (code "100") (name "VCC") (class "Default")
      (node (ref "C1") (pin "1") (pintype "passive"))
      (node (ref "C13") (pin "2") (pinfunction "2_2") (pintype "passive"))
      (node (ref "C3") (pin "2") (pinfunction "2_2") (pintype "passive"))
      (node (ref "D4") (pin "2") (pinfunction "2_2") (pintype "passive"))
      (node (ref "J1") (pin "1") (pinfunction "1_1") (pintype "passive"))
      (node (ref "J2") (pin "2") (pinfunction "2_2") (pintype "passive"))
      (node (ref "L1") (pin "2") (pinfunction "2_2") (pintype "passive"))
      (node (ref "P2") (pin "3") (pinfunction "3_3") (pintype "passive"))
      (node (ref "P7") (pin "3") (pinfunction "3_3") (pintype "passive"))
      (node (ref "P8") (pin "3") (pinfunction "3_3") (pintype "passive"))
      (node (ref "R1") (pin "2") (pinfunction "2_2") (pintype "passive"))
      (node (ref "R12") (pin "2") (pinfunction "2_2") (pintype "passive"))
      (node (ref "R16") (pin "2") (pinfunction "2_2") (pintype "passive"))
      (node (ref "R26") (pin "2") (pinfunction "2_2") (pintype "passive"))
      (node (ref "R27") (pin "2") (pinfunction "2_2") (pintype "passive"))
      (node (ref "R3") (pin "2") (pinfunction "2_2") (pintype "passive"))
      (node (ref "R32") (pin "1") (pinfunction "1_1") (pintype "passive"))
      (node (ref "R33") (pin "1") (pinfunction "1_1") (pintype "passive"))
      (node (ref "R35") (pin "1") (pinfunction "1_1") (pintype "passive"))
      (node (ref "R36") (pin "1") (pinfunction "1_1") (pintype "passive"))
      (node (ref "R41") (pin "2") (pinfunction "2_2") (pintype "passive"))
      (node (ref "R43") (pin "1") (pinfunction "1_1") (pintype "passive"))
      (node (ref "R44") (pin "1") (pinfunction "1_1") (pintype "passive"))
      (node (ref "R75") (pin "2") (pinfunction "2_2") (pintype "passive"))
      (node (ref "R77") (pin "2") (pinfunction "2_2") (pintype "passive"))
      (node (ref "R78") (pin "1") (pinfunction "1_1") (pintype "passive"))
      (node (ref "U2") (pin "3") (pinfunction "IN_3") (pintype "power_in"))
      (node (ref "U5") (pin "15") (pinfunction "VDD_15") (pintype "passive"))
      (node (ref "U6") (pin "15") (pinfunction "VDD_15") (pintype "passive"))
      (node (ref "U7") (pin "15") (pinfunction "VDD_15") (pintype "passive"))
      (node (ref "U9") (pin "5") (pinfunction "VCC_5") (pintype "passive"))
    )
    (net (code "101") (name "VUSB") (class "Default")
      (node (ref "C12") (pin "2") (pinfunction "2_2") (pintype "passive"))
      (node (ref "D4") (pin "1") (pinfunction "1_1") (pintype "passive"))
      (node (ref "D6") (pin "1") (pinfunction "1_1") (pintype "passive"))
      (node (ref "P3") (pin "A4") (pinfunction "VBUS_A4") (pintype "passive"))
      (node (ref "P3") (pin "A9") (pinfunction "VBUS_A9") (pintype "passive"))
      (node (ref "P3") (pin "B4") (pinfunction "VBUS_B4") (pintype "passive"))
      (node (ref "P3") (pin "B9") (pinfunction "VBUS_B9") (pintype "passive"))
    )
    (net (code "102") (name "unconnected-(P3-CC1-PadA5)") (class "Default")
      (node (ref "P3") (pin "A5") (pinfunction "CC1_A5") (pintype "passive"))
    )
    (net (code "103") (name "unconnected-(P3-CC2-PadB5)") (class "Default")
      (node (ref "P3") (pin "B5") (pinfunction "CC2_B5") (pintype "passive"))
    )
    (net (code "104") (name "unconnected-(P3-SUB1-PadA8)") (class "Default")
      (node (ref "P3") (pin "A8") (pinfunction "SUB1_A8") (pintype "passive"))
    )
    (net (code "105") (name "unconnected-(P3-SUB2-PadB8)") (class "Default")
      (node (ref "P3") (pin "B8") (pinfunction "SUB2_B8") (pintype "passive"))
    )
    (net (code "106") (name "unconnected-(TF1-DAT1-Pad8)") (class "Default")
      (node (ref "TF1") (pin "8") (pinfunction "DAT1_8") (pintype "passive"))
    )
    (net (code "107") (name "unconnected-(TF1-DAT2-Pad1)") (class "Default")
      (node (ref "TF1") (pin "1") (pinfunction "DAT2_1") (pintype "passive"))
    )
    (net (code "108") (name "unconnected-(U3-CLK-Pad20)") (class "Default")
      (node (ref "U3") (pin "20") (pinfunction "CLK_20") (pintype "passive"))
    )
    (net (code "109") (name "unconnected-(U3-CMD-Pad19)") (class "Default")
      (node (ref "U3") (pin "19") (pinfunction "CMD_19") (pintype "passive"))
    )
    (net (code "110") (name "unconnected-(U3-NC-Pad32)") (class "Default")
      (node (ref "U3") (pin "32") (pinfunction "NC_32") (pintype "passive"))
    )
    (net (code "111") (name "unconnected-(U3-SD0-Pad21)") (class "Default")
      (node (ref "U3") (pin "21") (pinfunction "SD0_21") (pintype "passive"))
    )
    (net (code "112") (name "unconnected-(U3-SD1-Pad22)") (class "Default")
      (node (ref "U3") (pin "22") (pinfunction "SD1_22") (pintype "passive"))
    )
    (net (code "113") (name "unconnected-(U3-SD2-Pad17)") (class "Default")
      (node (ref "U3") (pin "17") (pinfunction "SD2_17") (pintype "passive"))
    )
    (net (code "114") (name "unconnected-(U3-SD3-Pad18)") (class "Default")
      (node (ref "U3") (pin "18") (pinfunction "SD3_18") (pintype "passive"))
    )
    (net (code "115") (name "unconnected-(U4-Pad9)") (class "Default")
      (node (ref "U4") (pin "9") (pinfunction "9_9") (pintype "passive"))
    )
    (net (code "116") (name "unconnected-(U4-Pad10)") (class "Default")
      (node (ref "U4") (pin "10") (pinfunction "10_10") (pintype "passive"))
    )
    (net (code "117") (name "unconnected-(U4-Pad11)") (class "Default")
      (node (ref "U4") (pin "11") (pinfunction "11_11") (pintype "passive"))
    )
    (net (code "118") (name "unconnected-(U4-Pad12)") (class "Default")
      (node (ref "U4") (pin "12") (pinfunction "12_12") (pintype "passive"))
    )
    (net (code "119") (name "unconnected-(U4-Pad15)") (class "Default")
      (node (ref "U4") (pin "15") (pinfunction "15_15") (pintype "passive"))
    )
    (net (code "120") (name "unconnected-(U5-NC-Pad7)") (class "Default")
      (node (ref "U5") (pin "7") (pinfunction "NC_7") (pintype "passive"))
    )
    (net (code "121") (name "unconnected-(U5-NC-Pad20)") (class "Default")
      (node (ref "U5") (pin "20") (pinfunction "NC_20") (pintype "passive"))
    )
    (net (code "122") (name "unconnected-(U5-NC-Pad25)") (class "Default")
      (node (ref "U5") (pin "25") (pinfunction "NC_25") (pintype "passive"))
    )
    (net (code "123") (name "unconnected-(U6-NC-Pad7)") (class "Default")
      (node (ref "U6") (pin "7") (pinfunction "NC_7") (pintype "passive"))
    )
    (net (code "124") (name "unconnected-(U6-NC-Pad20)") (class "Default")
      (node (ref "U6") (pin "20") (pinfunction "NC_20") (pintype "passive"))
    )
    (net (code "125") (name "unconnected-(U6-NC-Pad25)") (class "Default")
      (node (ref "U6") (pin "25") (pinfunction "NC_25") (pintype "passive"))
    )
    (net (code "126") (name "unconnected-(U7-NC-Pad7)") (class "Default")
      (node (ref "U7") (pin "7") (pinfunction "NC_7") (pintype "passive"))
    )
    (net (code "127") (name "unconnected-(U7-NC-Pad20)") (class "Default")
      (node (ref "U7") (pin "20") (pinfunction "NC_20") (pintype "passive"))
    )
    (net (code "128") (name "unconnected-(U7-NC-Pad25)") (class "Default")
      (node (ref "U7") (pin "25") (pinfunction "NC_25") (pintype "passive"))
    )
    (net (code "129") (name "unconnected-(U9-NC-Pad1)") (class "Default")
      (node (ref "U9") (pin "1") (pinfunction "NC_1") (pintype "passive"))
    )
  )
)
